# ADC121C021-VSSOP.net
KiCad netlist of a schematic drawn in EAGLE
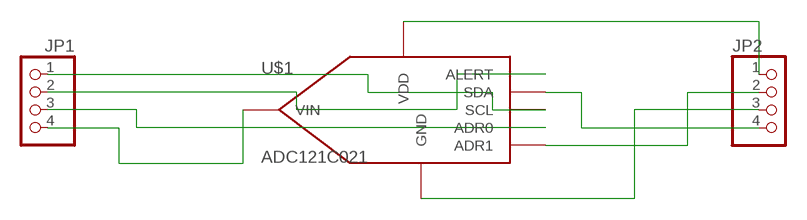
[diagram p0: schematic, sheet 1]

(export (version "E")
  (design (tool "Eeschema 10.0.6"))
  (components
    (comp (ref "JP1")
      (value "PINHD-1X4")
      (footprint "eagle-import:1X04")
      (libsource (lib "eagle-import") (part "PINHD-1X4"))
    )
    (comp (ref "JP2")
      (value "PINHD-1X4")
      (footprint "eagle-import:1X04")
      (libsource (lib "eagle-import") (part "PINHD-1X4"))
    )
    (comp (ref "U$1")
      (value "ADC121C021")
      (footprint "eagle-import:VSSOP-8")
      (libsource (lib "eagle-import") (part "ADC121C021"))
    )
  )
  (nets
    (net (code "1") (name "Net-(U$1-ADR0)") (class "Default")
      (node (ref "JP1") (pin "3") (pinfunction "3_3") (pintype "passive"))
      (node (ref "U$1") (pin "P$3") (pinfunction "ADR0_P$3") (pintype "bidirectional"))
    )
    (net (code "2") (name "Net-(U$1-ADR1)") (class "Default")
      (node (ref "JP2") (pin "2") (pinfunction "2_2") (pintype "passive"))
      (node (ref "U$1") (pin "P$6") (pinfunction "ADR1_P$6") (pintype "bidirectional"))
    )
    (net (code "3") (name "Net-(U$1-ALERT)") (class "Default")
      (node (ref "JP1") (pin "2") (pinfunction "2_2") (pintype "passive"))
      (node (ref "U$1") (pin "P$2") (pinfunction "ALERT_P$2") (pintype "bidirectional"))
    )
    (net (code "4") (name "Net-(U$1-GND)") (class "Default")
      (node (ref "JP2") (pin "3") (pinfunction "3_3") (pintype "passive"))
      (node (ref "U$1") (pin "P$7") (pinfunction "GND_P$7") (pintype "bidirectional"))
    )
    (net (code "5") (name "Net-(U$1-SCL)") (class "Default")
      (node (ref "JP1") (pin "1") (pinfunction "1_1") (pintype "passive"))
      (node (ref "U$1") (pin "P$1") (pinfunction "SCL_P$1") (pintype "bidirectional"))
    )
    (net (code "6") (name "Net-(U$1-SDA)") (class "Default")
      (node (ref "JP2") (pin "4") (pinfunction "4_4") (pintype "passive"))
      (node (ref "U$1") (pin "P$8") (pinfunction "SDA_P$8") (pintype "bidirectional"))
    )
    (net (code "7") (name "Net-(U$1-VDD)") (class "Default")
      (node (ref "JP2") (pin "1") (pinfunction "1_1") (pintype "passive"))
      (node (ref "U$1") (pin "P$5") (pinfunction "VDD_P$5") (pintype "bidirectional"))
    )
    (net (code "8") (name "Net-(U$1-VIN)") (class "Default")
      (node (ref "JP1") (pin "4") (pinfunction "4_4") (pintype "passive"))
      (node (ref "U$1") (pin "P$4") (pinfunction "VIN_P$4") (pintype "bidirectional"))
    )
  )
)
